# fpga_mio.net
KiCad netlist of a schematic drawn in Altium Designer
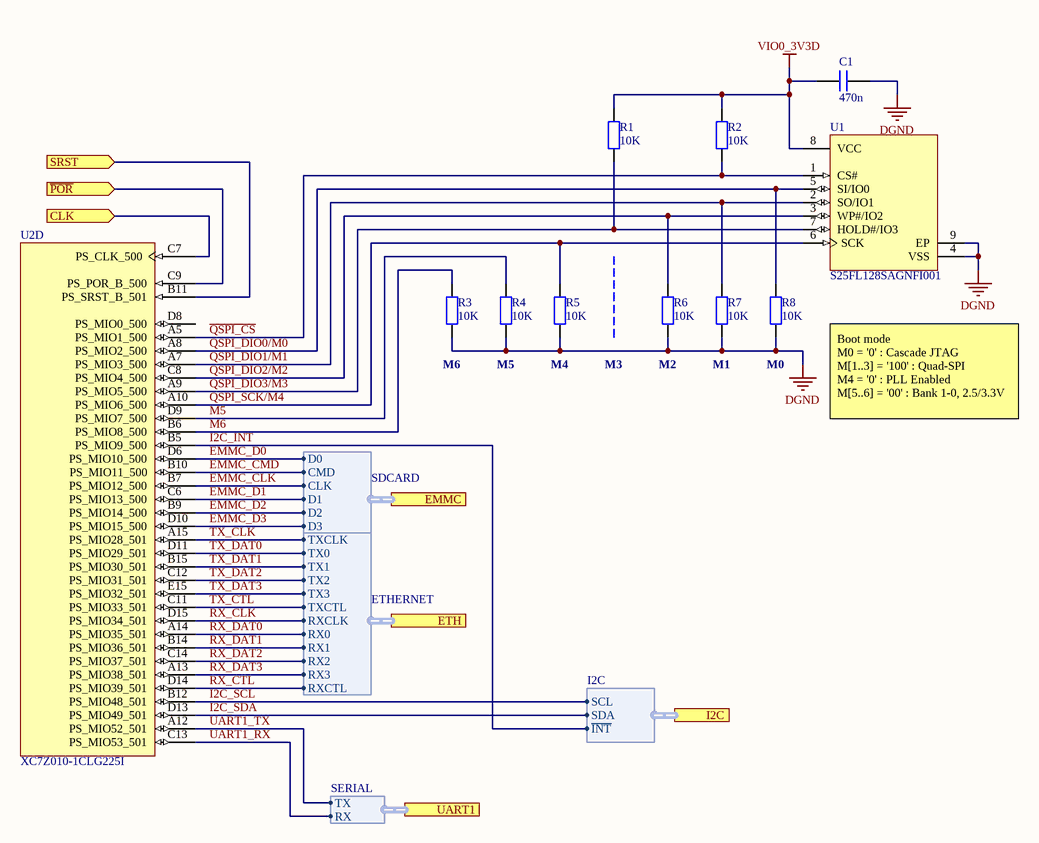
[diagram p0: fpga_mio.SchDoc]

(export (version "E")
  (design (tool "Eeschema 10.0.6"))
  (components
    (comp (ref "C1")
      (value "470n")
      (footprint "CAPC1608X08N")
      (description "Capacitor")
      (fields (field (name "Comment") "cap"))
      (libsource (lib "lib_passives") (part "cap"))
    )
    (comp (ref "R1")
      (value "10K")
      (footprint "RESC1005X04N")
      (description "Resistor")
      (fields (field (name "Comment") "res"))
      (libsource (lib "lib_passives") (part "res"))
    )
    (comp (ref "R2")
      (value "10K")
      (footprint "RESC1005X04N")
      (description "Resistor")
      (fields (field (name "Comment") "res"))
      (libsource (lib "lib_passives") (part "res"))
    )
    (comp (ref "R3")
      (value "10K")
      (footprint "RESC1005X04N")
      (description "Resistor")
      (fields (field (name "Comment") "res"))
      (libsource (lib "lib_passives") (part "res"))
    )
    (comp (ref "R4")
      (value "10K")
      (footprint "RESC1005X04N")
      (description "Resistor")
      (fields (field (name "Comment") "res"))
      (libsource (lib "lib_passives") (part "res"))
    )
    (comp (ref "R5")
      (value "10K")
      (footprint "RESC1005X04N")
      (description "Resistor")
      (fields (field (name "Comment") "res"))
      (libsource (lib "lib_passives") (part "res"))
    )
    (comp (ref "R6")
      (value "10K")
      (footprint "RESC1005X04N")
      (description "Resistor")
      (fields (field (name "Comment") "res"))
      (libsource (lib "lib_passives") (part "res"))
    )
    (comp (ref "R7")
      (value "10K")
      (footprint "RESC1005X04N")
      (description "Resistor")
      (fields (field (name "Comment") "res"))
      (libsource (lib "lib_passives") (part "res"))
    )
    (comp (ref "R8")
      (value "10K")
      (footprint "RESC1005X04N")
      (description "Resistor")
      (fields (field (name "Comment") "res"))
      (libsource (lib "lib_passives") (part "res"))
    )
    (comp (ref "U1")
      (value "S25FL128SAGNFI001")
      (footprint "SPSN-WSON-8_N")
      (fields (field (name "MANUFACTURER") "Spansion"))
      (libsource (lib "Altium Content Vault") (part "SPSN-S25FL128S-8"))
    )
    (comp (ref "U2")
      (value "XC7Z010-1CLG225I")
      (footprint "CLG225")
      (fields (field (name "GENERIC PART NUMBER") "XC7Z010"))
      (libsource (lib "Altium Content Vault") (part "XNLX-XC7Z010-CLG225"))
    )
  )
  (nets
    (net (code "5") (name "/CLK") (class "Default")
      (node (ref "U2") (pin "C7") (pinfunction "PS_CLK_500_C7") (pintype "input"))
    )
    (net (code "6") (name "/EMMC_CLK") (class "Default")
      (node (ref "U2") (pin "B7") (pinfunction "PS_MIO12_500_B7") (pintype "bidirectional"))
    )
    (net (code "7") (name "/EMMC_CMD") (class "Default")
      (node (ref "U2") (pin "B10") (pinfunction "PS_MIO11_500_B10") (pintype "bidirectional"))
    )
    (net (code "8") (name "/EMMC_D0") (class "Default")
      (node (ref "U2") (pin "D6") (pinfunction "PS_MIO10_500_D6") (pintype "bidirectional"))
    )
    (net (code "9") (name "/EMMC_D1") (class "Default")
      (node (ref "U2") (pin "C6") (pinfunction "PS_MIO13_500_C6") (pintype "bidirectional"))
    )
    (net (code "10") (name "/EMMC_D2") (class "Default")
      (node (ref "U2") (pin "B9") (pinfunction "PS_MIO14_500_B9") (pintype "bidirectional"))
    )
    (net (code "11") (name "/EMMC_D3") (class "Default")
      (node (ref "U2") (pin "D10") (pinfunction "PS_MIO15_500_D10") (pintype "bidirectional"))
    )
    (net (code "12") (name "/I2C_INT") (class "Default")
      (node (ref "U2") (pin "B5") (pinfunction "PS_MIO9_500_B5") (pintype "bidirectional"))
    )
    (net (code "13") (name "/I2C_SCL") (class "Default")
      (node (ref "U2") (pin "B12") (pinfunction "PS_MIO48_501_B12") (pintype "bidirectional"))
    )
    (net (code "14") (name "/I2C_SDA") (class "Default")
      (node (ref "U2") (pin "D13") (pinfunction "PS_MIO49_501_D13") (pintype "bidirectional"))
    )
    (net (code "15") (name "/M5") (class "Default")
      (node (ref "R4") (pin "2") (pinfunction "2_2") (pintype "passive"))
      (node (ref "U2") (pin "D9") (pinfunction "PS_MIO7_500_D9") (pintype "bidirectional"))
    )
    (net (code "16") (name "/M6") (class "Default")
      (node (ref "R3") (pin "2") (pinfunction "2_2") (pintype "passive"))
      (node (ref "U2") (pin "B6") (pinfunction "PS_MIO8_500_B6") (pintype "bidirectional"))
    )
    (net (code "17") (name "/POR") (class "Default")
      (node (ref "U2") (pin "C9") (pinfunction "PS_POR_B_500_C9") (pintype "input"))
    )
    (net (code "18") (name "/QSPI_CS") (class "Default")
      (node (ref "R2") (pin "1") (pinfunction "1_1") (pintype "passive"))
      (node (ref "U1") (pin "1") (pinfunction "CS#_1") (pintype "input"))
      (node (ref "U2") (pin "A5") (pinfunction "PS_MIO1_500_A5") (pintype "bidirectional"))
    )
    (net (code "19") (name "/QSPI_DIO0{slash}M0") (class "Default")
      (node (ref "R8") (pin "2") (pinfunction "2_2") (pintype "passive"))
      (node (ref "U1") (pin "5") (pinfunction "SI/IO0_5") (pintype "bidirectional"))
      (node (ref "U2") (pin "A8") (pinfunction "PS_MIO2_500_A8") (pintype "bidirectional"))
    )
    (net (code "20") (name "/QSPI_DIO1{slash}M1") (class "Default")
      (node (ref "R7") (pin "2") (pinfunction "2_2") (pintype "passive"))
      (node (ref "U1") (pin "2") (pinfunction "SO/IO1_2") (pintype "bidirectional"))
      (node (ref "U2") (pin "A7") (pinfunction "PS_MIO3_500_A7") (pintype "bidirectional"))
    )
    (net (code "21") (name "/QSPI_DIO2{slash}M2") (class "Default")
      (node (ref "R6") (pin "2") (pinfunction "2_2") (pintype "passive"))
      (node (ref "U1") (pin "3") (pinfunction "WP#/IO2_3") (pintype "bidirectional"))
      (node (ref "U2") (pin "C8") (pinfunction "PS_MIO4_500_C8") (pintype "bidirectional"))
    )
    (net (code "22") (name "/QSPI_DIO3{slash}M3") (class "Default")
      (node (ref "R1") (pin "1") (pinfunction "1_1") (pintype "passive"))
      (node (ref "U1") (pin "7") (pinfunction "HOLD#/IO3_7") (pintype "bidirectional"))
      (node (ref "U2") (pin "A9") (pinfunction "PS_MIO5_500_A9") (pintype "bidirectional"))
    )
    (net (code "23") (name "/QSPI_SCK{slash}M4") (class "Default")
      (node (ref "R5") (pin "2") (pinfunction "2_2") (pintype "passive"))
      (node (ref "U1") (pin "6") (pinfunction "SCK_6") (pintype "input"))
      (node (ref "U2") (pin "A10") (pinfunction "PS_MIO6_500_A10") (pintype "bidirectional"))
    )
    (net (code "24") (name "/RX_CLK") (class "Default")
      (node (ref "U2") (pin "D15") (pinfunction "PS_MIO34_501_D15") (pintype "bidirectional"))
    )
    (net (code "25") (name "/RX_CTL") (class "Default")
      (node (ref "U2") (pin "D14") (pinfunction "PS_MIO39_501_D14") (pintype "bidirectional"))
    )
    (net (code "26") (name "/RX_DAT0") (class "Default")
      (node (ref "U2") (pin "A14") (pinfunction "PS_MIO35_501_A14") (pintype "bidirectional"))
    )
    (net (code "27") (name "/RX_DAT1") (class "Default")
      (node (ref "U2") (pin "B14") (pinfunction "PS_MIO36_501_B14") (pintype "bidirectional"))
    )
    (net (code "28") (name "/RX_DAT2") (class "Default")
      (node (ref "U2") (pin "C14") (pinfunction "PS_MIO37_501_C14") (pintype "bidirectional"))
    )
    (net (code "29") (name "/RX_DAT3") (class "Default")
      (node (ref "U2") (pin "A13") (pinfunction "PS_MIO38_501_A13") (pintype "bidirectional"))
    )
    (net (code "30") (name "/SRST") (class "Default")
      (node (ref "U2") (pin "B11") (pinfunction "PS_SRST_B_501_B11") (pintype "input"))
    )
    (net (code "31") (name "/TX_CLK") (class "Default")
      (node (ref "U2") (pin "A15") (pinfunction "PS_MIO28_501_A15") (pintype "bidirectional"))
    )
    (net (code "32") (name "/TX_CTL") (class "Default")
      (node (ref "U2") (pin "C11") (pinfunction "PS_MIO33_501_C11") (pintype "bidirectional"))
    )
    (net (code "33") (name "/TX_DAT0") (class "Default")
      (node (ref "U2") (pin "D11") (pinfunction "PS_MIO29_501_D11") (pintype "bidirectional"))
    )
    (net (code "34") (name "/TX_DAT1") (class "Default")
      (node (ref "U2") (pin "B15") (pinfunction "PS_MIO30_501_B15") (pintype "bidirectional"))
    )
    (net (code "35") (name "/TX_DAT2") (class "Default")
      (node (ref "U2") (pin "C12") (pinfunction "PS_MIO31_501_C12") (pintype "bidirectional"))
    )
    (net (code "36") (name "/TX_DAT3") (class "Default")
      (node (ref "U2") (pin "E15") (pinfunction "PS_MIO32_501_E15") (pintype "bidirectional"))
    )
    (net (code "37") (name "/UART1_RX") (class "Default")
      (node (ref "U2") (pin "C13") (pinfunction "PS_MIO53_501_C13") (pintype "bidirectional"))
    )
    (net (code "38") (name "/UART1_TX") (class "Default")
      (node (ref "U2") (pin "A12") (pinfunction "PS_MIO52_501_A12") (pintype "bidirectional"))
    )
    (net (code "43") (name "DGND") (class "Default")
      (node (ref "C1") (pin "1") (pinfunction "1_1") (pintype "passive"))
      (node (ref "R3") (pin "1") (pinfunction "1_1") (pintype "passive"))
      (node (ref "R4") (pin "1") (pinfunction "1_1") (pintype "passive"))
      (node (ref "R5") (pin "1") (pinfunction "1_1") (pintype "passive"))
      (node (ref "R6") (pin "1") (pinfunction "1_1") (pintype "passive"))
      (node (ref "R7") (pin "1") (pinfunction "1_1") (pintype "passive"))
      (node (ref "R8") (pin "1") (pinfunction "1_1") (pintype "passive"))
      (node (ref "U1") (pin "4") (pinfunction "VSS_4") (pintype "power_in"))
      (node (ref "U1") (pin "9") (pinfunction "EP_9") (pintype "power_in"))
    )
    (net (code "44") (name "VIO0_3V3D") (class "Default")
      (node (ref "C1") (pin "2") (pinfunction "2_2") (pintype "passive"))
      (node (ref "R1") (pin "2") (pinfunction "2_2") (pintype "passive"))
      (node (ref "R2") (pin "2") (pinfunction "2_2") (pintype "passive"))
      (node (ref "U1") (pin "8") (pinfunction "VCC_8") (pintype "power_in"))
    )
    (net (code "45") (name "unconnected-(U2D-PS_MIO0_500-PadD8)") (class "Default")
      (node (ref "U2") (pin "D8") (pinfunction "PS_MIO0_500_D8") (pintype "bidirectional"))
    )
  )
)
